# onboarding_nathanlin.net
KiCad netlist of a schematic drawn in Altium Designer
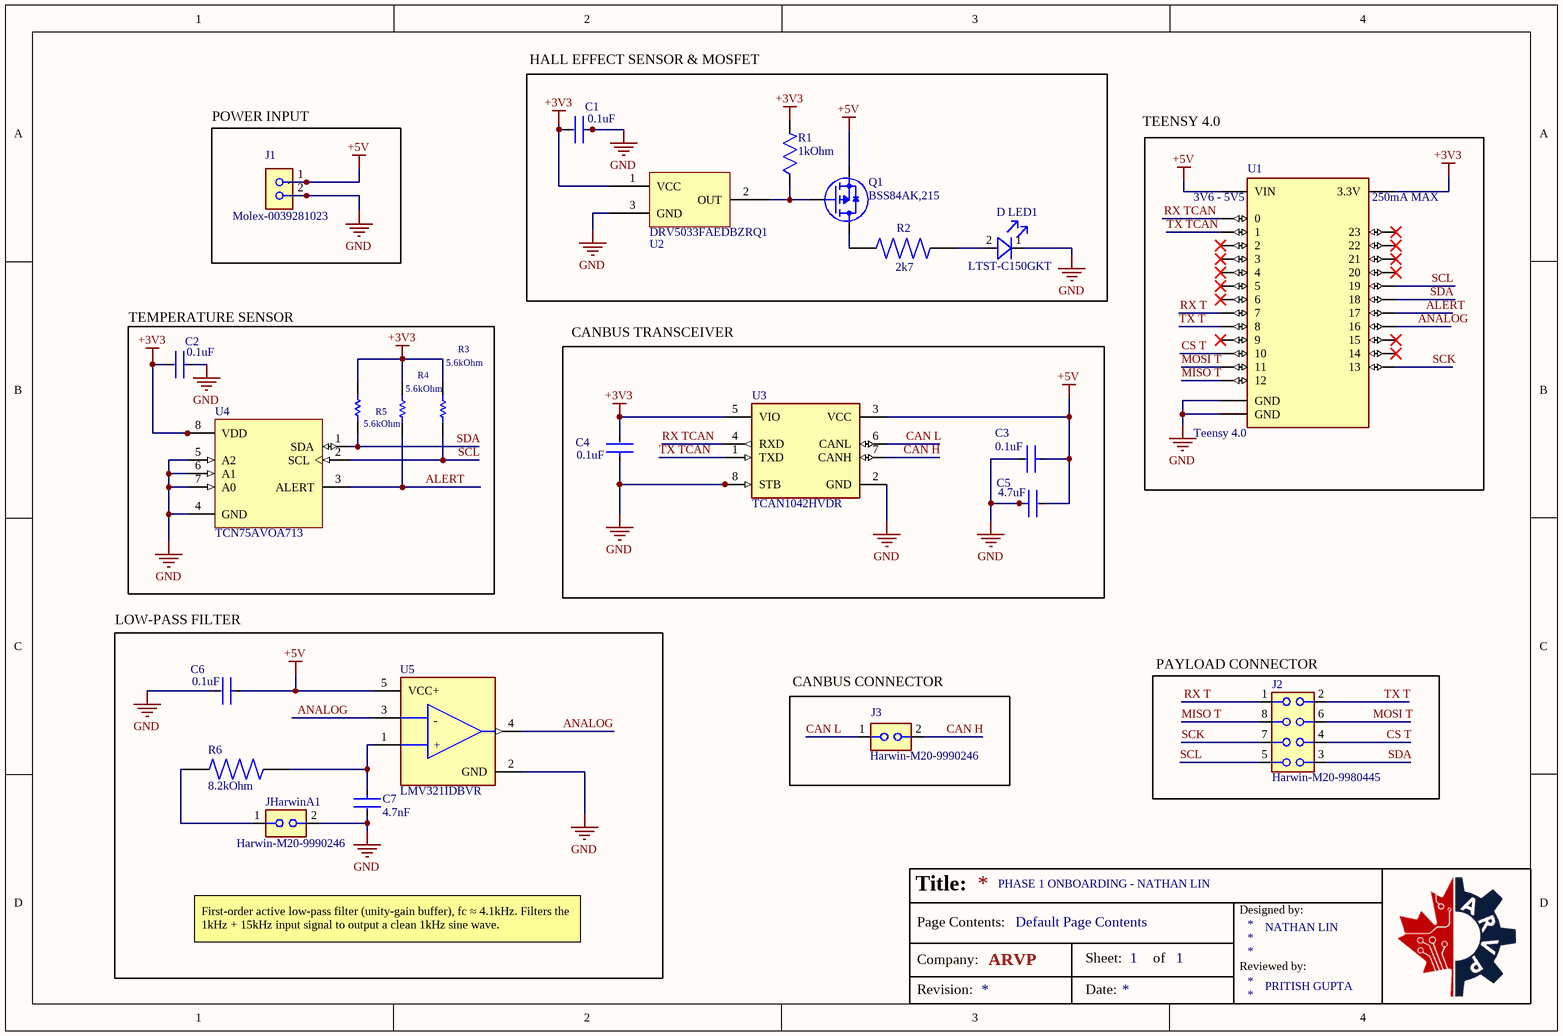
[diagram p0: onboarding_nathanlin.SchDoc]

(export (version "E")
  (design (tool "Eeschema 10.0.6"))
  (components
    (comp (ref "C1")
      (value "0.1uF")
      (footprint "CAP_0603")
      (description "CAP CER 0.1UF 50V X7R 0603")
      (fields (field (name "JLCPCB PART NO.") "C14663"))
      (libsource (lib "Autonomous Robotic Vehicle Project (ARVP)- University of Alberta") (part "CAP_UNPOLARIZED"))
    )
    (comp (ref "C2")
      (value "0.1uF")
      (footprint "CAP_0603")
      (description "CAP CER 0.1UF 50V X7R 0603")
      (fields (field (name "JLCPCB PART NO.") "C14663"))
      (libsource (lib "Autonomous Robotic Vehicle Project (ARVP)- University of Alberta") (part "CAP_UNPOLARIZED"))
    )
    (comp (ref "C3")
      (value "0.1uF")
      (footprint "CAP_0603")
      (description "CAP CER 0.1UF 50V X7R 0603")
      (fields (field (name "JLCPCB PART NO.") "C14663"))
      (libsource (lib "Autonomous Robotic Vehicle Project (ARVP)- University of Alberta") (part "CAP_UNPOLARIZED"))
    )
    (comp (ref "C4")
      (value "0.1uF")
      (footprint "CAP_0603")
      (description "CAP CER 0.1UF 50V X7R 0603")
      (fields (field (name "JLCPCB PART NO.") "C14663"))
      (libsource (lib "Autonomous Robotic Vehicle Project (ARVP)- University of Alberta") (part "CAP_UNPOLARIZED"))
    )
    (comp (ref "C5")
      (value "4.7uF")
      (footprint "CAP_0603")
      (description "CAP CER 4.7UF 16V X5R 0603")
      (fields (field (name "JLCPCB PART NO.") "C19666"))
      (libsource (lib "Autonomous Robotic Vehicle Project (ARVP)- University of Alberta") (part "CAP_UNPOLARIZED"))
    )
    (comp (ref "C6")
      (value "0.1uF")
      (footprint "CAP_0603")
      (description "CAP CER 0.1UF 50V X7R 0603")
      (fields (field (name "JLCPCB PART NO.") "C14663"))
      (libsource (lib "Autonomous Robotic Vehicle Project (ARVP)- University of Alberta") (part "CAP_UNPOLARIZED"))
    )
    (comp (ref "C7")
      (value "4.7nF")
      (footprint "CAP_0603")
      (description "4700 pF ±10% 50V Ceramic Capacitor X7R 0603 (1608 Metric)")
      (fields (field (name "JLCPCB PART NO.") "C1621"))
      (libsource (lib "Autonomous Robotic Vehicle Project (ARVP)- University of Alberta") (part "CAP_UNPOLARIZED"))
    )
    (comp (ref "D LED1")
      (value "LTST-C150GKT")
      (footprint "LED_1206")
      (description "LED GREEN CLEAR 1206 SMD")
      (fields (field (name "JLCPCB PART NO.") "C125084"))
      (libsource (lib "Autonomous Robotic Vehicle Project (ARVP)- University of Alberta") (part "LED"))
    )
    (comp (ref "J1")
      (value "Molex-0039281023")
      (footprint "0039281023")
      (description "Connector Header Through Hole 2 position")
      (fields (field (name "JLCPCB PART NO.") "C9900017326"))
      (libsource (lib "Autonomous Robotic Vehicle Project (ARVP)- University of Alberta") (part "0039281023"))
    )
    (comp (ref "J2")
      (value "Harwin-M20-9980445")
      (footprint "HARWIN_M20-9980445")
      (description "Connector Header Through Hole 8 position 0.100\" (2.54mm)")
      (fields (field (name "JLCPCB PART NO.") "C6897587") (field (name "MF") "Harwin Inc."))
      (libsource (lib "Autonomous Robotic Vehicle Project (ARVP)- University of Alberta") (part "M20-9980445"))
    )
    (comp (ref "J3")
      (value "Harwin-M20-9990246")
      (footprint "HARWIN_M20-9990246")
      (description "Connector Header Through Hole 2 position 0.100\" (2.54mm)")
      (fields (field (name "JLCPCB PART NO.") "C3332353"))
      (libsource (lib "Autonomous Robotic Vehicle Project (ARVP)- University of Alberta") (part "M20-9990246"))
    )
    (comp (ref "JHarwinA1")
      (value "Harwin-M20-9990246")
      (footprint "HARWIN_M20-9990246")
      (description "Connector Header Through Hole 2 position 0.100\" (2.54mm)")
      (fields (field (name "JLCPCB PART NO.") "C3332353"))
      (libsource (lib "Autonomous Robotic Vehicle Project (ARVP)- University of Alberta") (part "M20-9990246"))
    )
    (comp (ref "Q1")
      (value "BSS84AK,215")
      (footprint "Nexperia_SOT-23-3")
      (description "P-Channel 50 V 180mA (Ta) 350mW (Ta), 1.14W (Tc) Surface Mount TO-236AB")
      (fields (field (name "JLCPCB PART NO.") "C127273"))
      (libsource (lib "Autonomous Robotic Vehicle Project (ARVP)- University of Alberta") (part "BSS84AK,215"))
    )
    (comp (ref "R1")
      (value "1kOhm")
      (footprint "RES_0603")
      (description "1 kOhms ±1% 0.1W, 1/10W Chip Resistor 0603 (1608 Metric) Moisture Resistant Thick Film")
      (fields (field (name "POWER") "100mW") (field (name "TOLERANCE") "1%"))
      (libsource (lib "Autonomous Robotic Vehicle Project (ARVP)- University of Alberta") (part "RES"))
    )
    (comp (ref "R2")
      (value "2k7")
      (footprint "RESC1608X55N")
      (description "2.7 kOhms Â±5% 0.1W, 1/10W Chip Resistor 0603 (1608 Metric) Moisture Resistant Thick Film")
      (fields (field (name "MP") "RC0603JR-072K7L") (field (name "MF") "Yageo"))
      (libsource (lib "Autonomous Robotic Vehicle Project (ARVP)- University of Alberta") (part "RC0603JR-072K7L"))
    )
    (comp (ref "R3")
      (value "5.6kOhm")
      (footprint "RESC1608X55X30LL15T15")
      (description "Res Thick Film 0603 5.6K Ohm 5% 1/10W ±200ppm/°C Molded SMD Punched Carrier T/R")
      (libsource (lib "") (part "RES_1"))
    )
    (comp (ref "R4")
      (value "5.6kOhm")
      (footprint "RESC1608X55X30LL15T15")
      (description "Res Thick Film 0603 5.6K Ohm 5% 1/10W ±200ppm/°C Molded SMD Punched Carrier T/R")
      (libsource (lib "") (part "RES_1"))
    )
    (comp (ref "R5")
      (value "5.6kOhm")
      (footprint "RESC1608X55X30LL15T15")
      (description "Res Thick Film 0603 5.6K Ohm 5% 1/10W ±200ppm/°C Molded SMD Punched Carrier T/R")
      (libsource (lib "") (part "RES_1"))
    )
    (comp (ref "R6")
      (value "8.2kOhm")
      (footprint "RESC2012X60N")
      (description "8.2 kOhms Â±5% 0.125W, 1/8W Chip Resistor 0805 (2012 Metric) Moisture Resistant Thick Film")
      (fields (field (name "MF") "Yageo") (field (name "MP") "RC0805JR-078K2L"))
      (libsource (lib "Autonomous Robotic Vehicle Project (ARVP)- University of Alberta") (part "RC0805JR-078K2L"))
    )
    (comp (ref "U1")
      (value "Teensy 4.0")
      (footprint "TEENSY4.0")
      (description "RT1062 Teensy 4.0 i.MX ARM® Cortex®-M7 MPU Embedded Evaluation Board")
      (libsource (lib "Autonomous Robotic Vehicle Project (ARVP)- University of Alberta") (part "Teensy 4.0"))
    )
    (comp (ref "U2")
      (value "DRV5033FAEDBZRQ1")
      (footprint "TI_SOT-23-3")
      (description "Digital Switch Omnipolar Switch Open Drain Hall Effect SOT-23-3")
      (fields (field (name "JLCPCB PART NO.") "C2655029"))
      (libsource (lib "Autonomous Robotic Vehicle Project (ARVP)- University of Alberta") (part "DRV5033FAEDBZRQ1"))
    )
    (comp (ref "U3")
      (value "TCAN1042HVDR")
      (footprint "TI_SOIC8")
      (description "1/1 Transceiver CANbus 8-SOIC")
      (fields (field (name "JLCPCB PART NO.") "C127869"))
      (libsource (lib "Autonomous Robotic Vehicle Project (ARVP)- University of Alberta") (part "TCAN1042HVDR"))
    )
    (comp (ref "U4")
      (value "TCN75AVOA713")
      (footprint "Microchip_SOIC8")
      (description "Temperature Sensor Digital, Local -40°C ~ 125°C 11 b 8-SOIC")
      (fields (field (name "JLCPCB PART NO.") "C144313"))
      (libsource (lib "Autonomous Robotic Vehicle Project (ARVP)- University of Alberta") (part "TCN75AVOA713"))
    )
    (comp (ref "U5")
      (value "LMV321IDBVR")
      (footprint "SOT95P280X145-5N")
      (description "General Purpose Amplifier 1 Circuit Rail-to-Rail SOT-23-5")
      (fields (field (name "JLCPCB PART NO.") "C7972"))
      (libsource (lib "Autonomous Robotic Vehicle Project (ARVP)- University of Alberta") (part "LMV321IDBVR"))
    )
  )
  (nets
    (net (code "1") (name "+3V3") (class "Default")
      (node (ref "C1") (pin "2") (pinfunction "2_2") (pintype "passive"))
      (node (ref "C2") (pin "2") (pinfunction "2_2") (pintype "passive"))
      (node (ref "C4") (pin "2") (pinfunction "2_2") (pintype "passive"))
      (node (ref "R1") (pin "2") (pinfunction "2_2") (pintype "passive"))
      (node (ref "R3") (pin "2") (pinfunction "2_2") (pintype "passive"))
      (node (ref "R4") (pin "1") (pinfunction "1_1") (pintype "passive"))
      (node (ref "R5") (pin "1") (pinfunction "1_1") (pintype "passive"))
      (node (ref "U1") (pin "3.3V") (pinfunction "3.3V_3.3V") (pintype "power_in"))
      (node (ref "U2") (pin "1") (pinfunction "VCC_1") (pintype "power_in"))
      (node (ref "U3") (pin "5") (pinfunction "VIO_5") (pintype "power_in"))
      (node (ref "U4") (pin "8") (pinfunction "VDD_8") (pintype "power_in"))
    )
    (net (code "2") (name "+5V") (class "Default")
      (node (ref "C3") (pin "1") (pinfunction "1_1") (pintype "passive"))
      (node (ref "C5") (pin "2") (pinfunction "2_2") (pintype "passive"))
      (node (ref "C6") (pin "1") (pinfunction "1_1") (pintype "passive"))
      (node (ref "J1") (pin "1") (pinfunction "1_1") (pintype "passive"))
      (node (ref "Q1") (pin "2") (pinfunction "S_2") (pintype "passive"))
      (node (ref "U1") (pin "VIN") (pinfunction "VIN_VIN") (pintype "power_in"))
      (node (ref "U3") (pin "3") (pinfunction "VCC_3") (pintype "power_in"))
      (node (ref "U5") (pin "5") (pinfunction "VCC+_5") (pintype "power_in"))
    )
    (net (code "4") (name "/ALERT") (class "Default")
      (node (ref "R4") (pin "2") (pinfunction "2_2") (pintype "passive"))
      (node (ref "U1") (pin "17") (pinfunction "17_17") (pintype "bidirectional"))
      (node (ref "U4") (pin "3") (pinfunction "ALERT_3") (pintype "open_collector"))
    )
    (net (code "5") (name "/ANALOG") (class "Default")
      (node (ref "U1") (pin "16") (pinfunction "16_16") (pintype "bidirectional"))
      (node (ref "U5") (pin "3") (pinfunction "1IN-_3") (pintype "passive"))
      (node (ref "U5") (pin "4") (pinfunction "OUT_4") (pintype "output"))
    )
    (net (code "6") (name "/CAN H") (class "Default")
      (node (ref "J3") (pin "2") (pinfunction "2_2") (pintype "passive"))
      (node (ref "U3") (pin "7") (pinfunction "CANH_7") (pintype "bidirectional"))
    )
    (net (code "7") (name "/CAN L") (class "Default")
      (node (ref "J3") (pin "1") (pinfunction "1_1") (pintype "passive"))
      (node (ref "U3") (pin "6") (pinfunction "CANL_6") (pintype "bidirectional"))
    )
    (net (code "8") (name "/CS T") (class "Default")
      (node (ref "J2") (pin "4") (pinfunction "4_4") (pintype "passive"))
      (node (ref "U1") (pin "10") (pinfunction "10_10") (pintype "bidirectional"))
    )
    (net (code "9") (name "/MISO T") (class "Default")
      (node (ref "J2") (pin "8") (pinfunction "8_8") (pintype "passive"))
      (node (ref "U1") (pin "12") (pinfunction "12_12") (pintype "bidirectional"))
    )
    (net (code "10") (name "/MOSI T") (class "Default")
      (node (ref "J2") (pin "6") (pinfunction "6_6") (pintype "passive"))
      (node (ref "U1") (pin "11") (pinfunction "11_11") (pintype "bidirectional"))
    )
    (net (code "11") (name "/RX T") (class "Default")
      (node (ref "J2") (pin "1") (pinfunction "1_1") (pintype "passive"))
      (node (ref "U1") (pin "7") (pinfunction "7_7") (pintype "bidirectional"))
    )
    (net (code "12") (name "/RX TCAN") (class "Default")
      (node (ref "U1") (pin "0") (pinfunction "0_0") (pintype "bidirectional"))
      (node (ref "U3") (pin "4") (pinfunction "RXD_4") (pintype "output"))
    )
    (net (code "13") (name "/SCK") (class "Default")
      (node (ref "J2") (pin "7") (pinfunction "7_7") (pintype "passive"))
      (node (ref "U1") (pin "13") (pinfunction "13_13") (pintype "bidirectional"))
    )
    (net (code "14") (name "/SCL") (class "Default")
      (node (ref "J2") (pin "5") (pinfunction "5_5") (pintype "passive"))
      (node (ref "R3") (pin "1") (pinfunction "1_1") (pintype "passive"))
      (node (ref "U1") (pin "19") (pinfunction "19_19") (pintype "bidirectional"))
      (node (ref "U4") (pin "2") (pinfunction "SCL_2") (pintype "input"))
    )
    (net (code "15") (name "/SDA") (class "Default")
      (node (ref "J2") (pin "3") (pinfunction "3_3") (pintype "passive"))
      (node (ref "R5") (pin "2") (pinfunction "2_2") (pintype "passive"))
      (node (ref "U1") (pin "18") (pinfunction "18_18") (pintype "bidirectional"))
      (node (ref "U4") (pin "1") (pinfunction "SDA_1") (pintype "bidirectional"))
    )
    (net (code "16") (name "/TX T") (class "Default")
      (node (ref "J2") (pin "2") (pinfunction "2_2") (pintype "passive"))
      (node (ref "U1") (pin "8") (pinfunction "8_8") (pintype "bidirectional"))
    )
    (net (code "17") (name "/TX TCAN") (class "Default")
      (node (ref "U1") (pin "1") (pinfunction "1_1") (pintype "bidirectional"))
      (node (ref "U3") (pin "1") (pinfunction "TXD_1") (pintype "input"))
    )
    (net (code "18") (name "GND") (class "Default")
      (node (ref "C1") (pin "1") (pinfunction "1_1") (pintype "passive"))
      (node (ref "C2") (pin "1") (pinfunction "1_1") (pintype "passive"))
      (node (ref "C3") (pin "2") (pinfunction "2_2") (pintype "passive"))
      (node (ref "C4") (pin "1") (pinfunction "1_1") (pintype "passive"))
      (node (ref "C5") (pin "1") (pinfunction "1_1") (pintype "passive"))
      (node (ref "C6") (pin "2") (pinfunction "2_2") (pintype "passive"))
      (node (ref "C7") (pin "2") (pinfunction "2_2") (pintype "passive"))
      (node (ref "D LED1") (pin "1") (pinfunction "C_1") (pintype "passive"))
      (node (ref "J1") (pin "2") (pinfunction "2_2") (pintype "passive"))
      (node (ref "JHarwinA1") (pin "2") (pinfunction "2_2") (pintype "passive"))
      (node (ref "U1") (pin "GND1") (pinfunction "GND_GND1") (pintype "passive"))
      (node (ref "U1") (pin "GND2") (pinfunction "GND_GND2") (pintype "passive"))
      (node (ref "U2") (pin "3") (pinfunction "GND_3") (pintype "power_in"))
      (node (ref "U3") (pin "2") (pinfunction "GND_2") (pintype "power_in"))
      (node (ref "U3") (pin "8") (pinfunction "STB_8") (pintype "input"))
      (node (ref "U4") (pin "4") (pinfunction "GND_4") (pintype "power_in"))
      (node (ref "U4") (pin "5") (pinfunction "A2_5") (pintype "input"))
      (node (ref "U4") (pin "6") (pinfunction "A1_6") (pintype "input"))
      (node (ref "U4") (pin "7") (pinfunction "A0_7") (pintype "input"))
      (node (ref "U5") (pin "2") (pinfunction "GND_2") (pintype "power_in"))
    )
    (net (code "19") (name "Net-(D LED1-A)") (class "Default")
      (node (ref "D LED1") (pin "2") (pinfunction "A_2") (pintype "passive"))
      (node (ref "R2") (pin "1") (pinfunction "1_1") (pintype "passive"))
    )
    (net (code "20") (name "Net-(JHarwinA1-Pad1)") (class "Default")
      (node (ref "JHarwinA1") (pin "1") (pinfunction "1_1") (pintype "passive"))
      (node (ref "R6") (pin "1") (pinfunction "1_1") (pintype "passive"))
    )
    (net (code "21") (name "Net-(Q1-D)") (class "Default")
      (node (ref "Q1") (pin "3") (pinfunction "D_3") (pintype "passive"))
      (node (ref "R2") (pin "2") (pinfunction "2_2") (pintype "passive"))
    )
    (net (code "22") (name "Net-(Q1-G)") (class "Default")
      (node (ref "Q1") (pin "1") (pinfunction "G_1") (pintype "passive"))
      (node (ref "R1") (pin "1") (pinfunction "1_1") (pintype "passive"))
      (node (ref "U2") (pin "2") (pinfunction "OUT_2") (pintype "open_collector"))
    )
    (net (code "23") (name "Net-(U5-1IN+)") (class "Default")
      (node (ref "C7") (pin "1") (pinfunction "1_1") (pintype "passive"))
      (node (ref "R6") (pin "2") (pinfunction "2_2") (pintype "passive"))
      (node (ref "U5") (pin "1") (pinfunction "1IN+_1") (pintype "passive"))
    )
    (net (code "24") (name "unconnected-(U1-Pad2)") (class "Default")
      (node (ref "U1") (pin "2") (pinfunction "2_2") (pintype "bidirectional+no_connect"))
    )
    (net (code "25") (name "unconnected-(U1-Pad3)") (class "Default")
      (node (ref "U1") (pin "3") (pinfunction "3_3") (pintype "bidirectional+no_connect"))
    )
    (net (code "26") (name "unconnected-(U1-Pad4)") (class "Default")
      (node (ref "U1") (pin "4") (pinfunction "4_4") (pintype "bidirectional+no_connect"))
    )
    (net (code "27") (name "unconnected-(U1-Pad5)") (class "Default")
      (node (ref "U1") (pin "5") (pinfunction "5_5") (pintype "bidirectional+no_connect"))
    )
    (net (code "28") (name "unconnected-(U1-Pad6)") (class "Default")
      (node (ref "U1") (pin "6") (pinfunction "6_6") (pintype "bidirectional+no_connect"))
    )
    (net (code "29") (name "unconnected-(U1-Pad9)") (class "Default")
      (node (ref "U1") (pin "9") (pinfunction "9_9") (pintype "bidirectional+no_connect"))
    )
    (net (code "30") (name "unconnected-(U1-Pad14)") (class "Default")
      (node (ref "U1") (pin "14") (pinfunction "14_14") (pintype "bidirectional+no_connect"))
    )
    (net (code "31") (name "unconnected-(U1-Pad15)") (class "Default")
      (node (ref "U1") (pin "15") (pinfunction "15_15") (pintype "bidirectional+no_connect"))
    )
    (net (code "32") (name "unconnected-(U1-Pad20)") (class "Default")
      (node (ref "U1") (pin "20") (pinfunction "20_20") (pintype "bidirectional+no_connect"))
    )
    (net (code "33") (name "unconnected-(U1-Pad21)") (class "Default")
      (node (ref "U1") (pin "21") (pinfunction "21_21") (pintype "bidirectional+no_connect"))
    )
    (net (code "34") (name "unconnected-(U1-Pad22)") (class "Default")
      (node (ref "U1") (pin "22") (pinfunction "22_22") (pintype "bidirectional+no_connect"))
    )
    (net (code "35") (name "unconnected-(U1-Pad23)") (class "Default")
      (node (ref "U1") (pin "23") (pinfunction "23_23") (pintype "bidirectional+no_connect"))
    )
  )
)
